# GyroCube_easyeda.net
KiCad netlist of a schematic drawn in EasyEDA
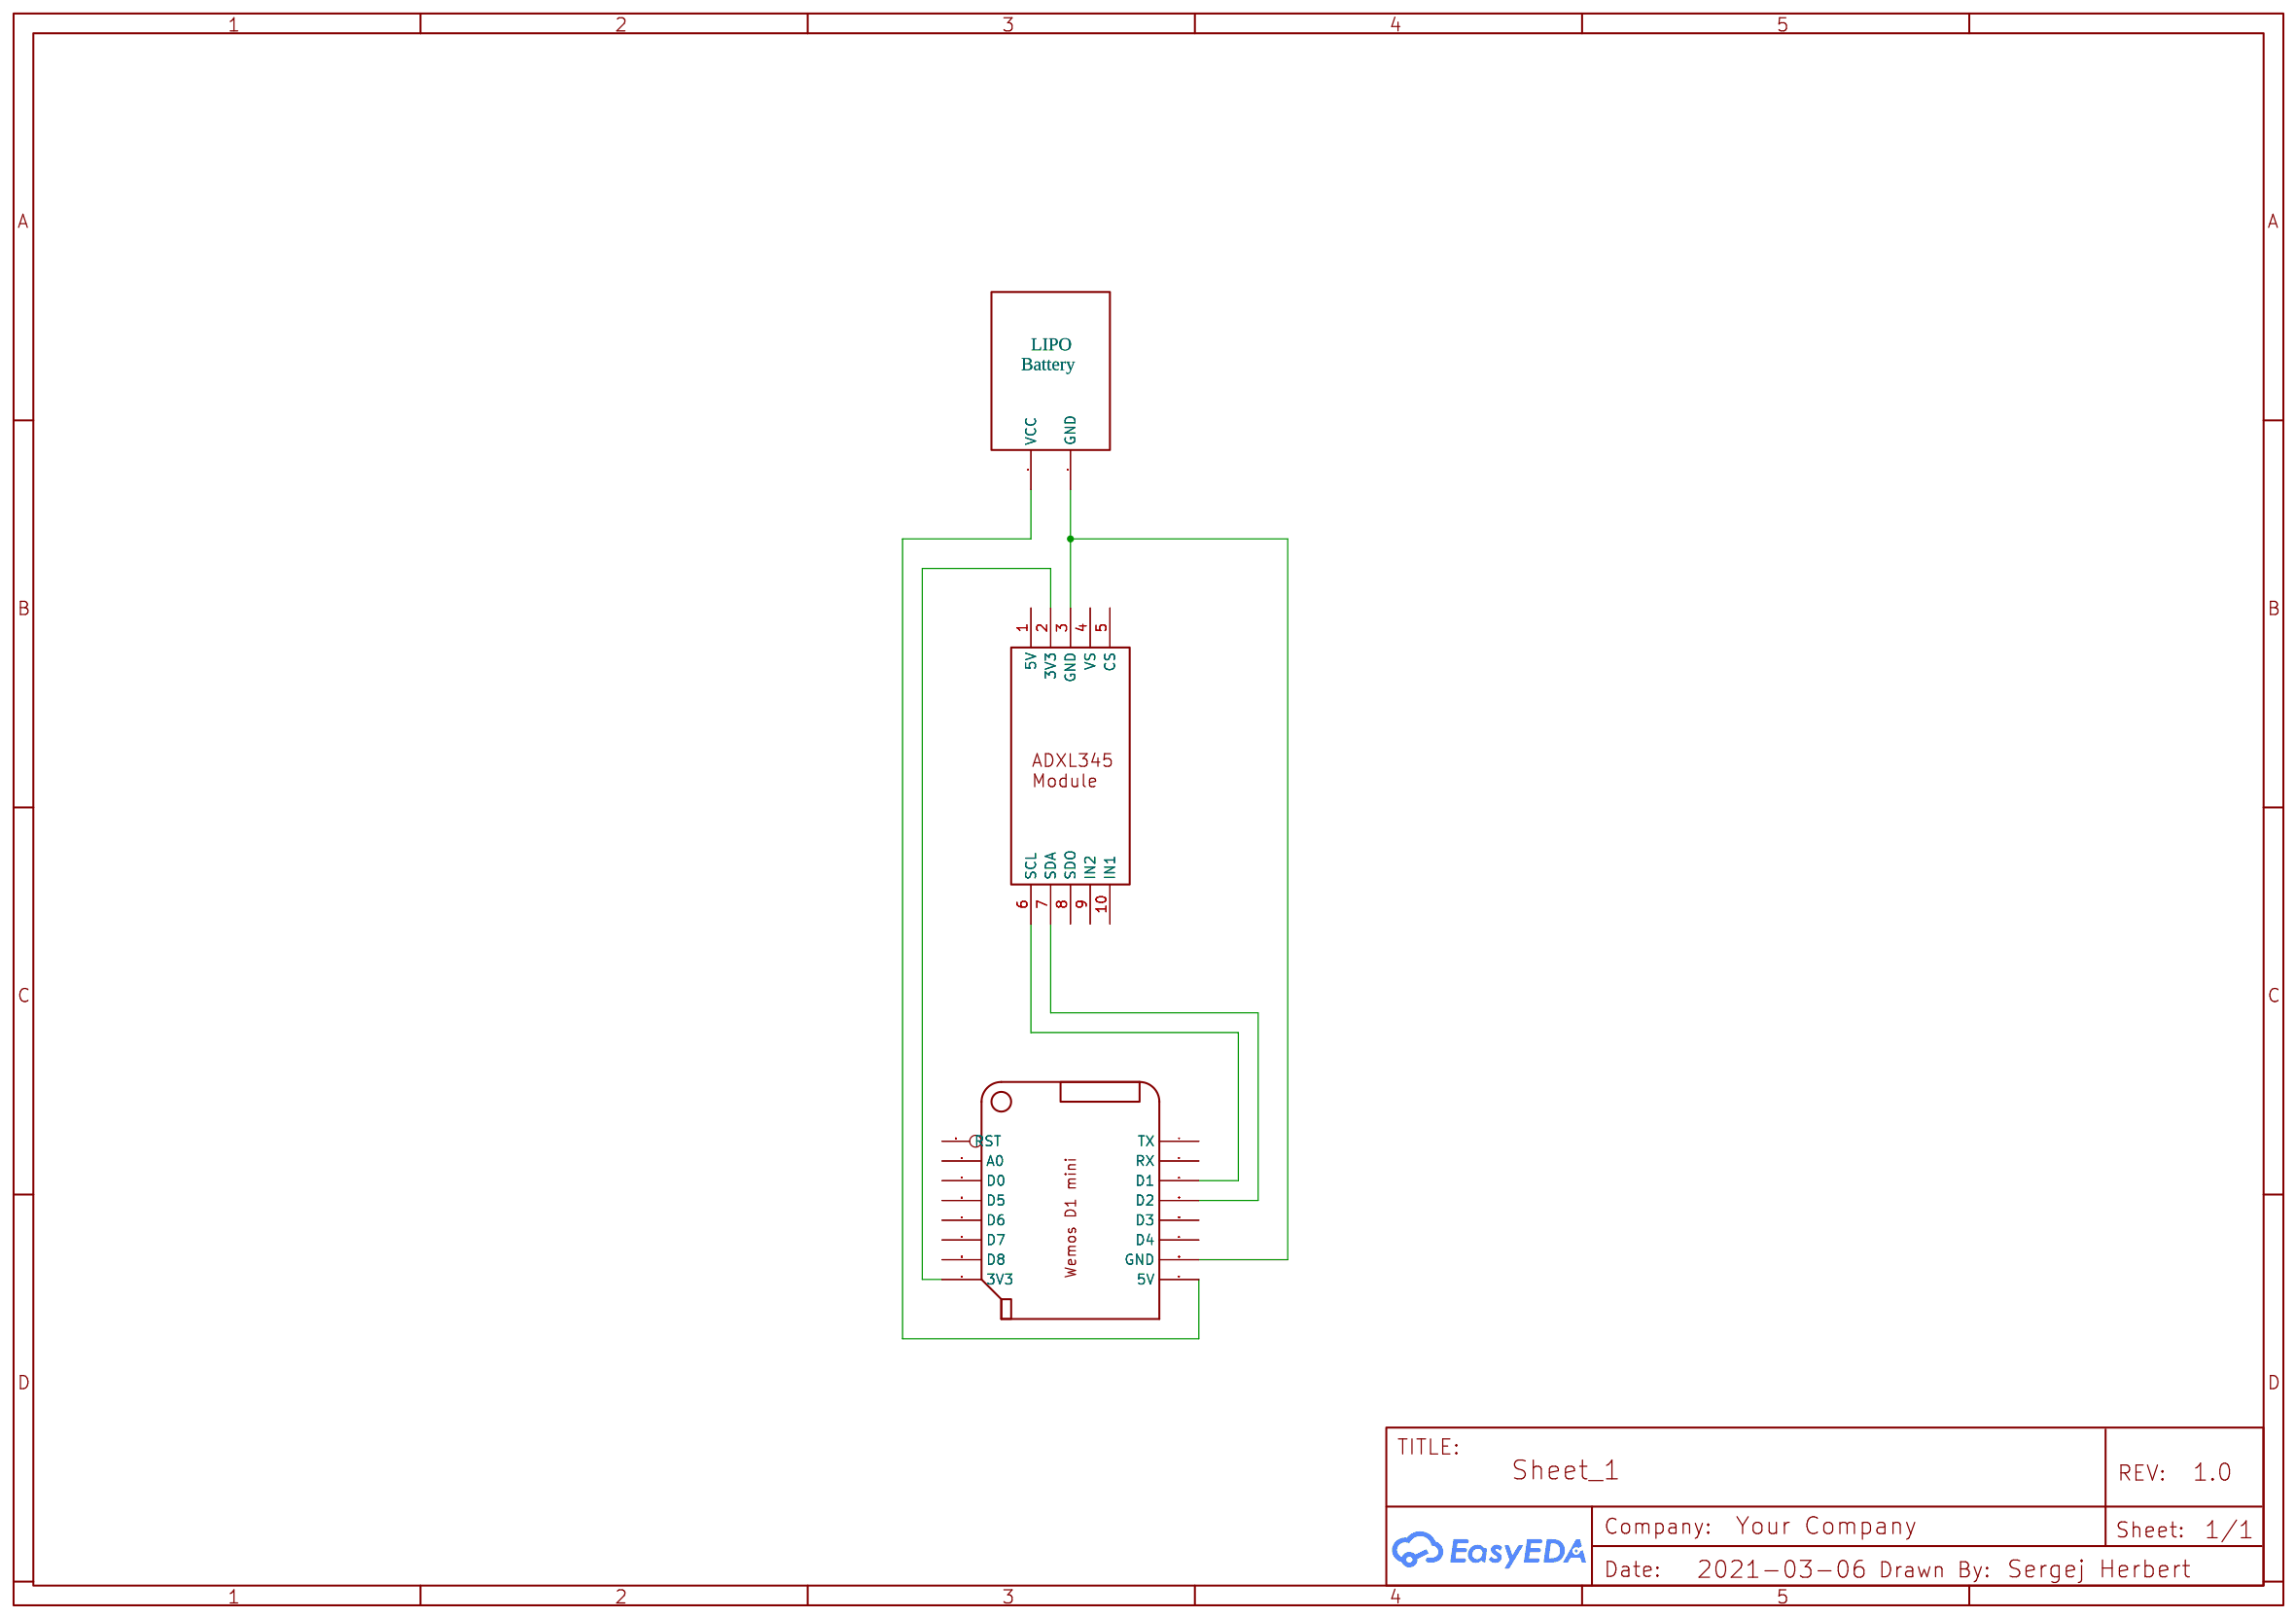
[diagram p0: schematic sheet]

(export (version "E")
  (design (tool "Eeschema 10.0.6"))
  (components
    (comp (ref "LIPO") (value "Battery") (libsource (lib "") (part "Unknown_525_-615")))
    (comp (ref "U2") (value "ADXL345") (libsource (lib "") (part "ADXL345")))
    (comp (ref "U3") (value "Wemos D1") (libsource (lib "") (part "Wemos D1")))
  )
  (nets
    (net (code "1") (name "Net-(LIPO-GND)") (class "Default")
      (node (ref "LIPO") (pin "2") (pinfunction "GND_2") (pintype "unspecified"))
      (node (ref "U2") (pin "3") (pinfunction "GND_3") (pintype "unspecified"))
      (node (ref "U3") (pin "GND") (pinfunction "GND_GND") (pintype "unspecified"))
    )
    (net (code "2") (name "Net-(LIPO-VCC)") (class "Default")
      (node (ref "LIPO") (pin "1") (pinfunction "VCC_1") (pintype "unspecified"))
      (node (ref "U3") (pin "5V") (pinfunction "5V_5V") (pintype "unspecified"))
    )
    (net (code "3") (name "Net-(U2-3V3)") (class "Default")
      (node (ref "U2") (pin "2") (pinfunction "3V3_2") (pintype "unspecified"))
      (node (ref "U3") (pin "3V3") (pinfunction "3V3_3V3") (pintype "unspecified"))
    )
    (net (code "4") (name "Net-(U2-SCL)") (class "Default")
      (node (ref "U2") (pin "6") (pinfunction "SCL_6") (pintype "unspecified"))
      (node (ref "U3") (pin "D1") (pinfunction "D1_D1") (pintype "unspecified"))
    )
    (net (code "5") (name "Net-(U2-SDA)") (class "Default")
      (node (ref "U2") (pin "7") (pinfunction "SDA_7") (pintype "unspecified"))
      (node (ref "U3") (pin "D2") (pinfunction "D2_D2") (pintype "unspecified"))
    )
    (net (code "6") (name "unconnected-(U2-5V-Pad1)") (class "Default")
      (node (ref "U2") (pin "1") (pinfunction "5V_1") (pintype "unspecified"))
    )
    (net (code "7") (name "unconnected-(U2-CS-Pad5)") (class "Default")
      (node (ref "U2") (pin "5") (pinfunction "CS_5") (pintype "unspecified"))
    )
    (net (code "8") (name "unconnected-(U2-IN1-Pad10)") (class "Default")
      (node (ref "U2") (pin "10") (pinfunction "IN1_10") (pintype "unspecified"))
    )
    (net (code "9") (name "unconnected-(U2-IN2-Pad9)") (class "Default")
      (node (ref "U2") (pin "9") (pinfunction "IN2_9") (pintype "unspecified"))
    )
    (net (code "10") (name "unconnected-(U2-SDO-Pad8)") (class "Default")
      (node (ref "U2") (pin "8") (pinfunction "SDO_8") (pintype "unspecified"))
    )
    (net (code "11") (name "unconnected-(U2-VS-Pad4)") (class "Default")
      (node (ref "U2") (pin "4") (pinfunction "VS_4") (pintype "unspecified"))
    )
    (net (code "12") (name "unconnected-(U3-PadA0)") (class "Default")
      (node (ref "U3") (pin "A0") (pinfunction "A0_A0") (pintype "unspecified"))
    )
    (net (code "13") (name "unconnected-(U3-PadD0)") (class "Default")
      (node (ref "U3") (pin "D0") (pinfunction "D0_D0") (pintype "unspecified"))
    )
    (net (code "14") (name "unconnected-(U3-PadD3)") (class "Default")
      (node (ref "U3") (pin "D3") (pinfunction "D3_D3") (pintype "unspecified"))
    )
    (net (code "15") (name "unconnected-(U3-PadD4)") (class "Default")
      (node (ref "U3") (pin "D4") (pinfunction "D4_D4") (pintype "unspecified"))
    )
    (net (code "16") (name "unconnected-(U3-PadD5)") (class "Default")
      (node (ref "U3") (pin "D5") (pinfunction "D5_D5") (pintype "unspecified"))
    )
    (net (code "17") (name "unconnected-(U3-PadD6)") (class "Default")
      (node (ref "U3") (pin "D6") (pinfunction "D6_D6") (pintype "unspecified"))
    )
    (net (code "18") (name "unconnected-(U3-PadD7)") (class "Default")
      (node (ref "U3") (pin "D7") (pinfunction "D7_D7") (pintype "unspecified"))
    )
    (net (code "19") (name "unconnected-(U3-PadD8)") (class "Default")
      (node (ref "U3") (pin "D8") (pinfunction "D8_D8") (pintype "unspecified"))
    )
    (net (code "20") (name "unconnected-(U3-PadRST)") (class "Default")
      (node (ref "U3") (pin "RST") (pinfunction "RST_RST") (pintype "unspecified"))
    )
    (net (code "21") (name "unconnected-(U3-PadRX)") (class "Default")
      (node (ref "U3") (pin "RX") (pinfunction "RX_RX") (pintype "unspecified"))
    )
    (net (code "22") (name "unconnected-(U3-PadTX)") (class "Default")
      (node (ref "U3") (pin "TX") (pinfunction "TX_TX") (pintype "unspecified"))
    )
  )
)
